# auto-discharge.net
KiCad netlist of a schematic drawn in Altium Designer
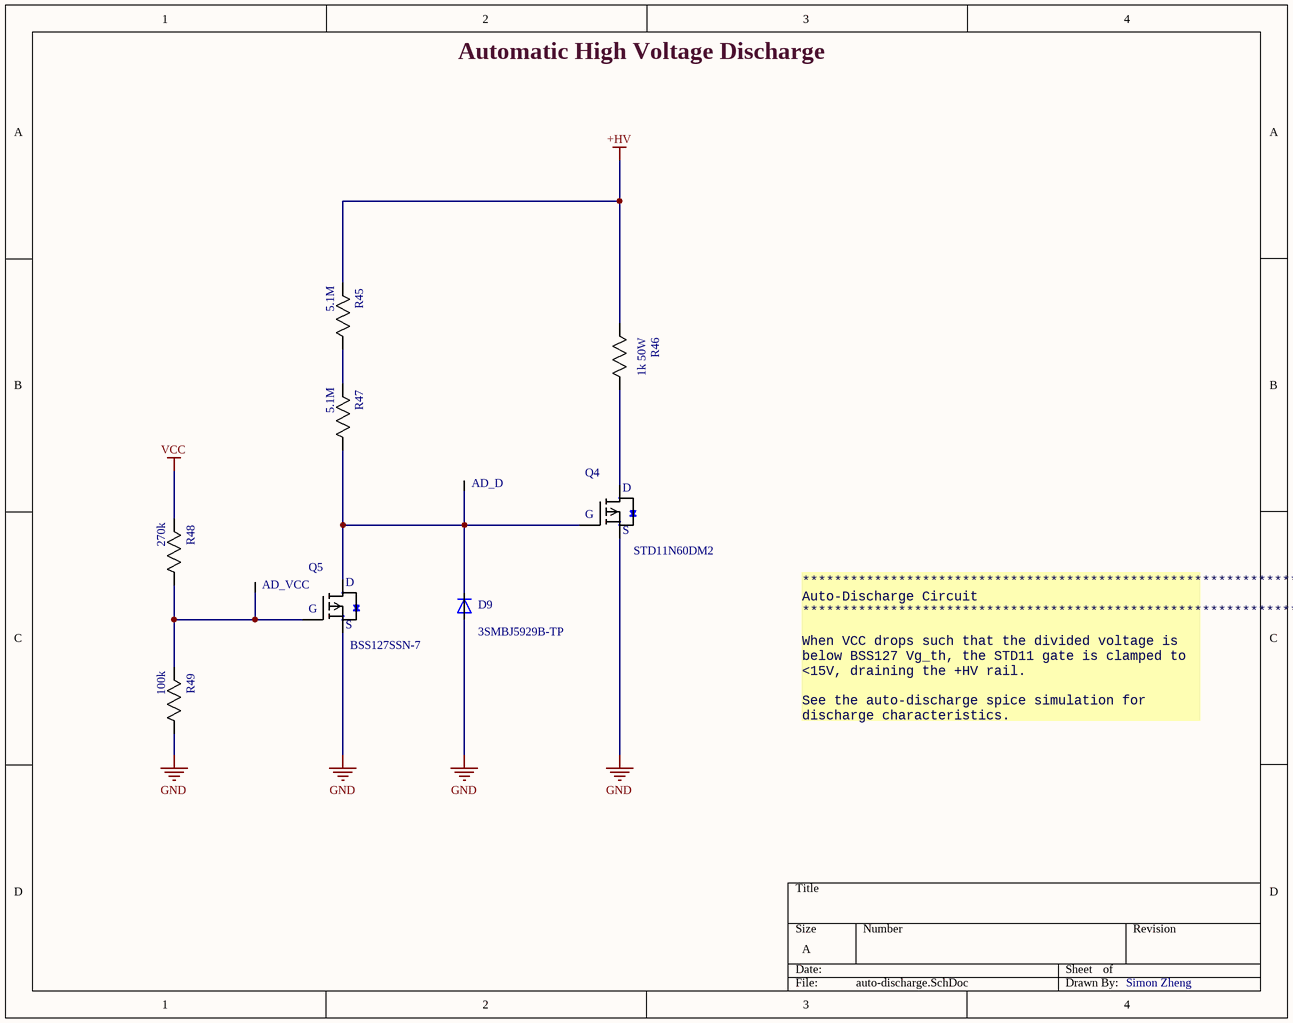
[diagram p0: auto-discharge.SchDoc]

(export (version "E")
  (design (tool "Eeschema 10.0.6"))
  (components
    (comp (ref "AD_D")
      (value "Test Point (Via)")
      (footprint "TP")
      (libsource (lib "AltiumLibraries") (part "Test Point (Via)"))
    )
    (comp (ref "AD_VCC")
      (value "Test Point (Via)")
      (footprint "TP")
      (libsource (lib "AltiumLibraries") (part "Test Point (Via)"))
    )
    (comp (ref "D9")
      (value "3SMBJ5929B-TP")
      (footprint "DO-214AA")
      (description "Diode ZENER 15V 3W")
      (libsource (lib "AltiumLibraries") (part "DIODE ZENER 15V 3W"))
    )
    (comp (ref "Q4")
      (value "STD11N60DM2")
      (footprint "DPAK (TO-252)")
      (fields (field (name "MFG") "STMicroelectronics"))
      (libsource (lib "AltiumLibraries") (part "STD11N60DM2"))
    )
    (comp (ref "Q5")
      (value "BSS127SSN-7")
      (footprint "SOT95P245X89-3M")
      (description "Small Signal N-Ch, 600Vds")
      (fields (field (name "MFG") "Diodes Incorporated"))
      (libsource (lib "AltiumLibraries") (part "BSS127SSN-7"))
    )
    (comp (ref "R45")
      (value "5.1M")
      (footprint "0805")
      (description "RES SMD 5.1 MOHM 5% 1/8W 0805")
      (fields (field (name "TOLERANCE") "5%"))
      (libsource (lib "AltiumLibraries") (part "RES 5.1M 1/8W-5%"))
    )
    (comp (ref "R46")
      (value "1k 50W")
      (footprint "D2PAK (TO-263)")
      (description "RES SMD 1.5K OHM 1% 50W D2PAK")
      (fields (field (name "TOLERANCE") "1%"))
      (libsource (lib "AltiumLibraries") (part "RES 1.5k 50W"))
    )
    (comp (ref "R47")
      (value "5.1M")
      (footprint "0805")
      (description "RES SMD 5.1 MOHM 5% 1/8W 0805")
      (fields (field (name "TOLERANCE") "5%"))
      (libsource (lib "") (part "RES 5.1M 1/8W-5%_1"))
    )
    (comp (ref "R48")
      (value "270k")
      (footprint "0805")
      (description "RES SMD 270K OHM 5% 1/8W 0805")
      (fields (field (name "TOLERANCE") "5%"))
      (libsource (lib "AltiumLibraries") (part "RES 270k 1/8W"))
    )
    (comp (ref "R49")
      (value "100k")
      (footprint "0805")
      (description "RES SMD 100K OHM 1% 1/8W 0805")
      (fields (field (name "TOLERANCE") "1%"))
      (libsource (lib "AltiumLibraries") (part "RES 100k 1/8W - 1%"))
    )
  )
  (nets
    (net (code "1") (name "+HV") (class "Default")
      (node (ref "R45") (pin "2") (pinfunction "R2_2") (pintype "passive"))
      (node (ref "R46") (pin "2") (pinfunction "R2_2") (pintype "passive"))
    )
    (net (code "2") (name "GND") (class "Default")
      (node (ref "D9") (pin "A") (pinfunction "A_A") (pintype "passive"))
      (node (ref "Q4") (pin "S") (pinfunction "S_S") (pintype "passive"))
      (node (ref "Q5") (pin "S") (pinfunction "S_S") (pintype "passive"))
      (node (ref "R49") (pin "1") (pinfunction "R1_1") (pintype "passive"))
    )
    (net (code "3") (name "Net-(R45-R1)") (class "Default")
      (node (ref "R45") (pin "1") (pinfunction "R1_1") (pintype "passive"))
      (node (ref "R47") (pin "2") (pinfunction "R2_2") (pintype "passive"))
    )
    (net (code "4") (name "Net-(R46-R1)") (class "Default")
      (node (ref "Q4") (pin "D") (pinfunction "D_D") (pintype "passive"))
      (node (ref "R46") (pin "1") (pinfunction "R1_1") (pintype "passive"))
    )
    (net (code "5") (name "Net-(R47-R1)") (class "Default")
      (node (ref "AD_D") (pin "1") (pinfunction "1_1") (pintype "passive"))
      (node (ref "D9") (pin "C") (pinfunction "C_C") (pintype "passive"))
      (node (ref "Q4") (pin "G") (pinfunction "G_G") (pintype "passive"))
      (node (ref "Q5") (pin "D") (pinfunction "D_D") (pintype "passive"))
      (node (ref "R47") (pin "1") (pinfunction "R1_1") (pintype "passive"))
    )
    (net (code "6") (name "Net-(R48-R1)") (class "Default")
      (node (ref "AD_VCC") (pin "1") (pinfunction "1_1") (pintype "passive"))
      (node (ref "Q5") (pin "G") (pinfunction "G_G") (pintype "passive"))
      (node (ref "R48") (pin "1") (pinfunction "R1_1") (pintype "passive"))
      (node (ref "R49") (pin "2") (pinfunction "R2_2") (pintype "passive"))
    )
    (net (code "7") (name "VCC") (class "Default")
      (node (ref "R48") (pin "2") (pinfunction "R2_2") (pintype "passive"))
    )
  )
)
